# DSP.net
KiCad netlist of a schematic drawn in Altium Designer
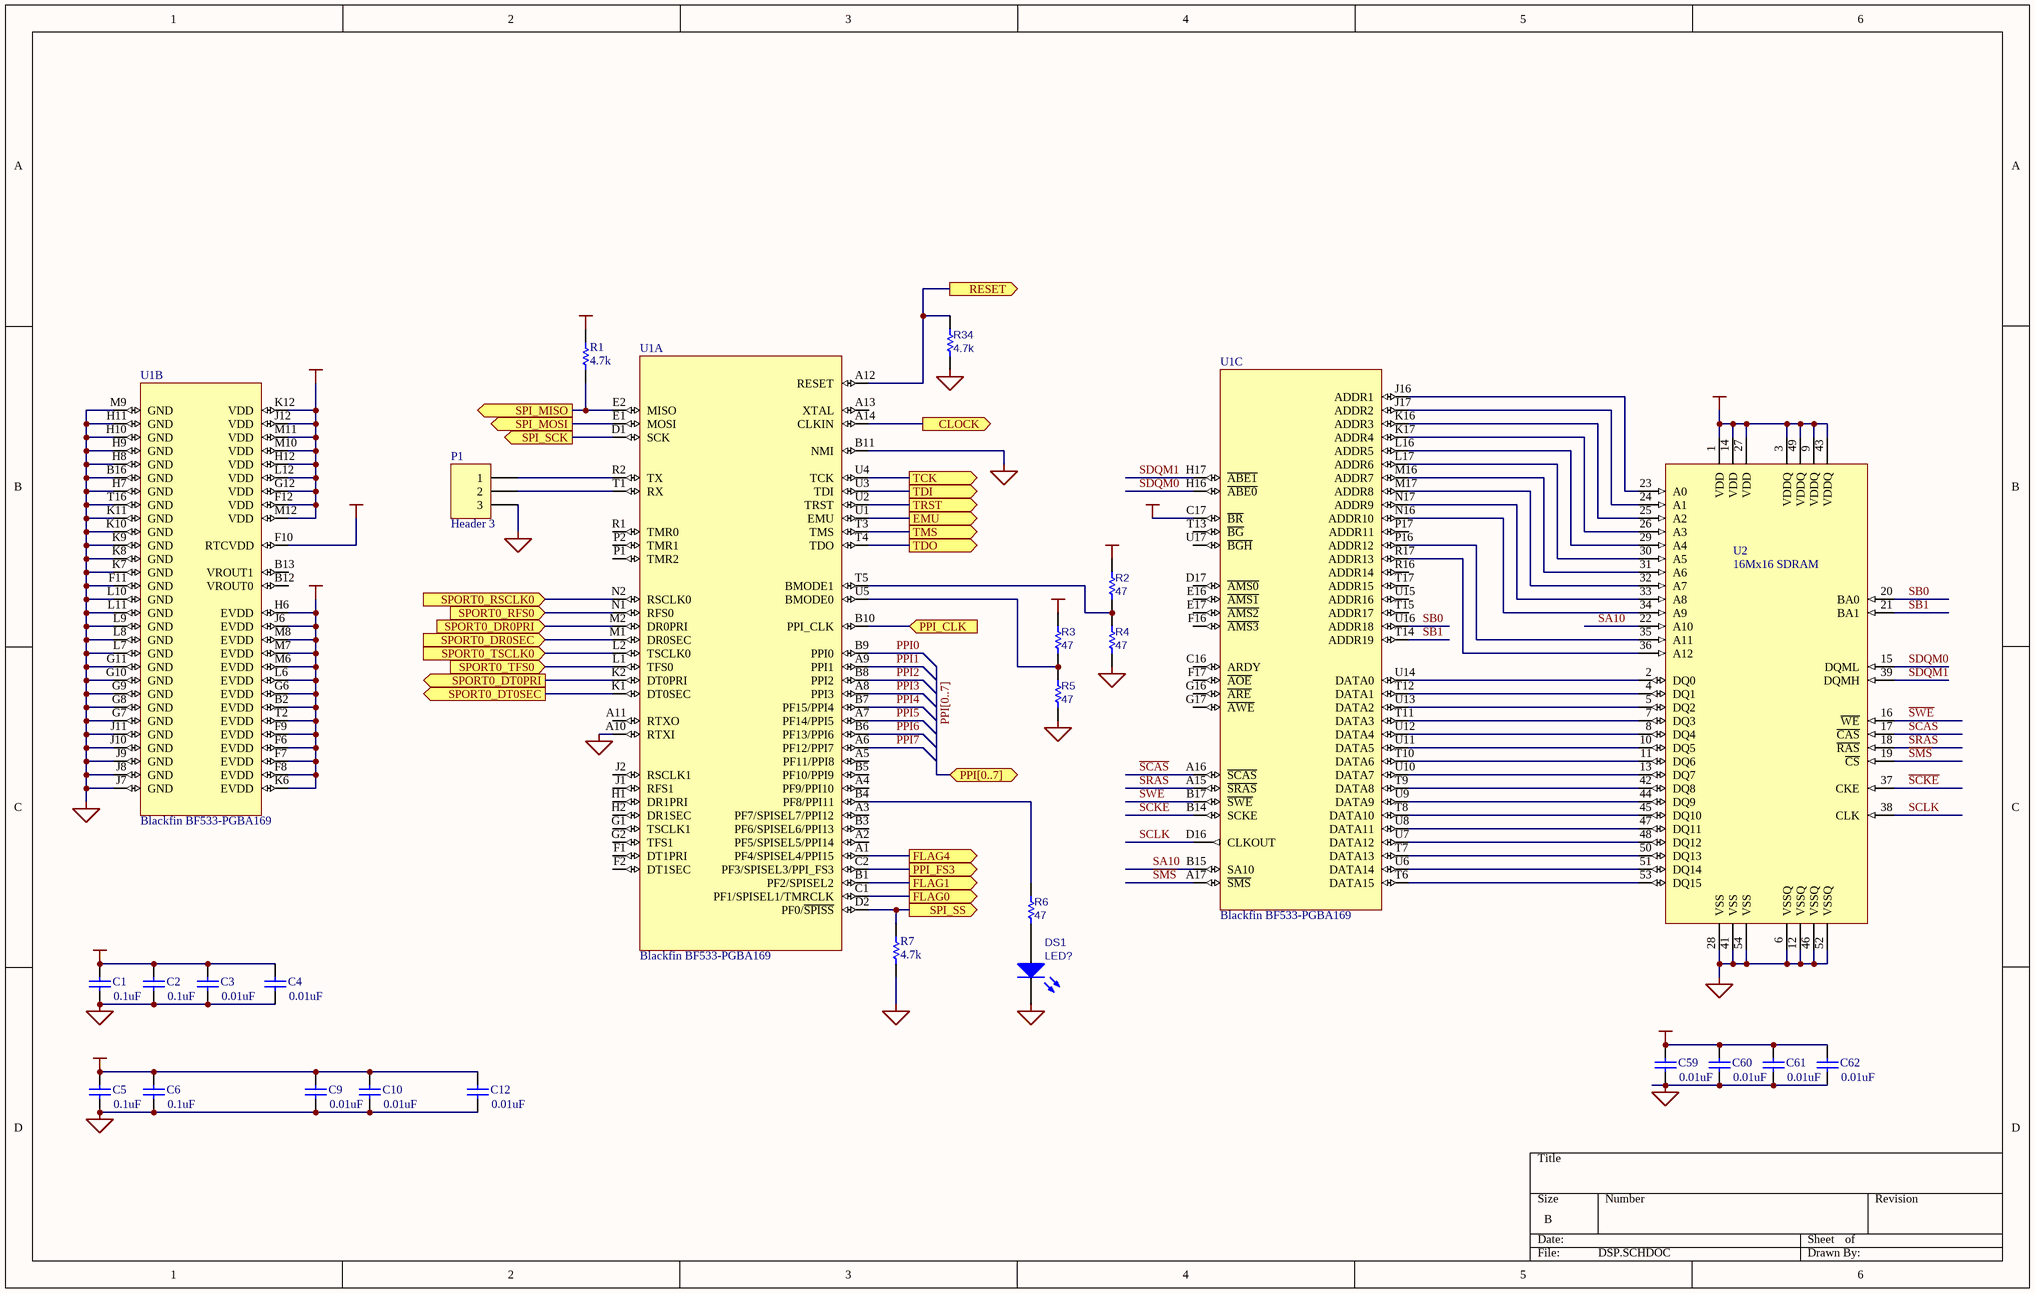
[diagram p0: DSP.SCHDOC]

(export (version "E")
  (design (tool "Eeschema 10.0.6"))
  (components
    (comp (ref "C1")
      (value "0.1uF")
      (footprint "CC1608-0603")
      (description "Capacitor")
      (fields (field (name "Comment") "Cap") (field (name "PUBLISHER") "Altium Limited"))
      (libsource (lib "Miscellaneous Devices") (part "Cap"))
    )
    (comp (ref "C2")
      (value "0.1uF")
      (footprint "CC1608-0603")
      (description "Capacitor")
      (fields (field (name "Comment") "Cap") (field (name "PUBLISHER") "Altium Limited"))
      (libsource (lib "Miscellaneous Devices") (part "Cap"))
    )
    (comp (ref "C3")
      (value "0.01uF")
      (footprint "CC1005-0402")
      (description "Capacitor")
      (fields (field (name "Comment") "Cap") (field (name "PUBLISHER") "Altium Limited"))
      (libsource (lib "Miscellaneous Devices") (part "Cap"))
    )
    (comp (ref "C4")
      (value "0.01uF")
      (footprint "CC1005-0402")
      (description "Capacitor")
      (fields (field (name "Comment") "Cap") (field (name "PUBLISHER") "Altium Limited"))
      (libsource (lib "Miscellaneous Devices") (part "Cap"))
    )
    (comp (ref "C5")
      (value "0.1uF")
      (footprint "CC1608-0603")
      (description "Capacitor")
      (fields (field (name "Comment") "Cap") (field (name "PUBLISHER") "Altium Limited"))
      (libsource (lib "Miscellaneous Devices") (part "Cap"))
    )
    (comp (ref "C6")
      (value "0.1uF")
      (footprint "CC1608-0603")
      (description "Capacitor")
      (fields (field (name "Comment") "Cap") (field (name "PUBLISHER") "Altium Limited"))
      (libsource (lib "Miscellaneous Devices") (part "Cap"))
    )
    (comp (ref "C9")
      (value "0.01uF")
      (footprint "CC1005-0402")
      (description "Capacitor")
      (fields (field (name "Comment") "Cap") (field (name "PUBLISHER") "Altium Limited"))
      (libsource (lib "Miscellaneous Devices") (part "Cap"))
    )
    (comp (ref "C10")
      (value "0.01uF")
      (footprint "CC1005-0402")
      (description "Capacitor")
      (fields (field (name "Comment") "Cap") (field (name "PUBLISHER") "Altium Limited"))
      (libsource (lib "Miscellaneous Devices") (part "Cap"))
    )
    (comp (ref "C12")
      (value "0.01uF")
      (footprint "CC1005-0402")
      (description "Capacitor")
      (fields (field (name "Comment") "Cap") (field (name "PUBLISHER") "Altium Limited"))
      (libsource (lib "Miscellaneous Devices") (part "Cap"))
    )
    (comp (ref "C59")
      (value "0.01uF")
      (footprint "CC1005-0402")
      (description "Capacitor")
      (fields (field (name "Comment") "Cap") (field (name "PUBLISHER") "Altium Limited"))
      (libsource (lib "Miscellaneous Devices") (part "Cap"))
    )
    (comp (ref "C60")
      (value "0.01uF")
      (footprint "CC1005-0402")
      (description "Capacitor")
      (fields (field (name "Comment") "Cap") (field (name "PUBLISHER") "Altium Limited"))
      (libsource (lib "Miscellaneous Devices") (part "Cap"))
    )
    (comp (ref "C61")
      (value "0.01uF")
      (footprint "CC1005-0402")
      (description "Capacitor")
      (fields (field (name "Comment") "Cap") (field (name "PUBLISHER") "Altium Limited"))
      (libsource (lib "Miscellaneous Devices") (part "Cap"))
    )
    (comp (ref "C62")
      (value "0.01uF")
      (footprint "CC1005-0402")
      (description "Capacitor")
      (fields (field (name "Comment") "Cap") (field (name "PUBLISHER") "Altium Limited"))
      (libsource (lib "Miscellaneous Devices") (part "Cap"))
    )
    (comp (ref "DS1")
      (value "LED?")
      (footprint "SMD _LED")
      (description "Typical BLUE SiC LED")
      (fields (field (name "PUBLISHER") "Altium Limited"))
      (libsource (lib "Miscellaneous Devices") (part "LED3"))
    )
    (comp (ref "P1")
      (value "Header 3")
      (footprint "HDR1X3")
      (description "Header, 3-Pin")
      (fields (field (name "PUBLISHER") "Altium Limited"))
      (libsource (lib "Miscellaneous Connectors") (part "Header 3"))
    )
    (comp (ref "R1")
      (value "4.7k")
      (footprint "CR1608-0603")
      (description "Resistor")
      (fields (field (name "PUBLISHER") "Altium Limited"))
      (libsource (lib "Miscellaneous Devices") (part "Res1"))
    )
    (comp (ref "R2")
      (value "47")
      (footprint "CR1608-0603")
      (description "Resistor")
      (fields
        (field (name "MANUFACTURER") "Generic Components")
        (field (name "Comment") "Res1")
        (field (name "PUBLISHER") "Altium Limited")
      )
      (libsource (lib "Miscellaneous Devices") (part "Res1"))
    )
    (comp (ref "R3")
      (value "47")
      (footprint "CR1608-0603")
      (description "Resistor")
      (fields
        (field (name "MANUFACTURER") "Generic Components")
        (field (name "Comment") "Res1")
        (field (name "PUBLISHER") "Altium Limited")
      )
      (libsource (lib "Miscellaneous Devices") (part "Res1"))
    )
    (comp (ref "R4")
      (value "47")
      (footprint "CR1608-0603")
      (description "Resistor")
      (fields
        (field (name "MANUFACTURER") "Generic Components")
        (field (name "Comment") "Res1")
        (field (name "PUBLISHER") "Altium Limited")
      )
      (libsource (lib "Miscellaneous Devices") (part "Res1"))
    )
    (comp (ref "R5")
      (value "47")
      (footprint "CR1608-0603")
      (description "Resistor")
      (fields
        (field (name "MANUFACTURER") "Generic Components")
        (field (name "Comment") "Res1")
        (field (name "PUBLISHER") "Altium Limited")
      )
      (libsource (lib "Miscellaneous Devices") (part "Res1"))
    )
    (comp (ref "R6")
      (value "47")
      (footprint "CR1608-0603")
      (description "Resistor")
      (fields
        (field (name "MANUFACTURER") "Generic Components")
        (field (name "Comment") "Res1")
        (field (name "PUBLISHER") "Altium Limited")
      )
      (libsource (lib "Miscellaneous Devices") (part "Res1"))
    )
    (comp (ref "R7")
      (value "4.7k")
      (footprint "CR1608-0603")
      (description "Resistor")
      (fields (field (name "PUBLISHER") "Altium Limited"))
      (libsource (lib "Miscellaneous Devices") (part "Res1"))
    )
    (comp (ref "R34")
      (value "4.7k")
      (footprint "CR1608-0603")
      (description "Resistor")
      (fields
        (field (name "MANUFACTURER") "Generic Components")
        (field (name "Comment") "Res1")
        (field (name "PUBLISHER") "Altium Limited")
      )
      (libsource (lib "Miscellaneous Devices") (part "Res1"))
    )
    (comp (ref "U1")
      (value "Blackfin BF533-PGBA169")
      (footprint "AD PBGA-169")
      (description "Analog Devices Blackfin")
      (libsource (lib "parts") (part "ADSP-BF53x-PBGA169"))
    )
    (comp (ref "U2")
      (value "16Mx16 SDRAM")
      (footprint "SO-G54/X.5")
      (description "Micron 16Mbitx16 SDRAM")
      (libsource (lib "parts") (part "MT48LC16M16A2TG"))
    )
  )
  (nets
    (net (code "1") (name "+1.2VCC") (class "Default")
      (node (ref "C1") (pin "2") (pinfunction "2_2") (pintype "passive"))
      (node (ref "C2") (pin "2") (pinfunction "2_2") (pintype "passive"))
      (node (ref "C3") (pin "2") (pinfunction "2_2") (pintype "passive"))
      (node (ref "C4") (pin "2") (pinfunction "2_2") (pintype "passive"))
      (node (ref "U1") (pin "F12") (pinfunction "VDD_F12") (pintype "bidirectional"))
      (node (ref "U1") (pin "G12") (pinfunction "VDD_G12") (pintype "bidirectional"))
      (node (ref "U1") (pin "H12") (pinfunction "VDD_H12") (pintype "bidirectional"))
      (node (ref "U1") (pin "J12") (pinfunction "VDD_J12") (pintype "bidirectional"))
      (node (ref "U1") (pin "K12") (pinfunction "VDD_K12") (pintype "bidirectional"))
      (node (ref "U1") (pin "L12") (pinfunction "VDD_L12") (pintype "bidirectional"))
      (node (ref "U1") (pin "M10") (pinfunction "VDD_M10") (pintype "bidirectional"))
      (node (ref "U1") (pin "M11") (pinfunction "VDD_M11") (pintype "bidirectional"))
      (node (ref "U1") (pin "M12") (pinfunction "VDD_M12") (pintype "bidirectional"))
    )
    (net (code "2") (name "/CLOCK") (class "Default")
      (node (ref "U1") (pin "A14") (pinfunction "CLKIN_A14") (pintype "bidirectional"))
    )
    (net (code "3") (name "/EMU") (class "Default")
      (node (ref "U1") (pin "U1") (pinfunction "EMU_U1") (pintype "bidirectional"))
    )
    (net (code "4") (name "/FLAG0") (class "Default")
      (node (ref "U1") (pin "C1") (pinfunction "PF1/SPISEL1/TMRCLK_C1") (pintype "bidirectional"))
    )
    (net (code "5") (name "/FLAG1") (class "Default")
      (node (ref "U1") (pin "B1") (pinfunction "PF2/SPISEL2_B1") (pintype "bidirectional"))
    )
    (net (code "6") (name "/FLAG4") (class "Default")
      (node (ref "U1") (pin "A1") (pinfunction "PF4/SPISEL4/PPI15_A1") (pintype "bidirectional"))
    )
    (net (code "7") (name "/PPI0") (class "Default")
      (node (ref "U1") (pin "B9") (pinfunction "PPI0_B9") (pintype "bidirectional"))
    )
    (net (code "8") (name "/PPI1") (class "Default")
      (node (ref "U1") (pin "A9") (pinfunction "PPI1_A9") (pintype "bidirectional"))
    )
    (net (code "9") (name "/PPI2") (class "Default")
      (node (ref "U1") (pin "B8") (pinfunction "PPI2_B8") (pintype "bidirectional"))
    )
    (net (code "10") (name "/PPI3") (class "Default")
      (node (ref "U1") (pin "A8") (pinfunction "PPI3_A8") (pintype "bidirectional"))
    )
    (net (code "11") (name "/PPI4") (class "Default")
      (node (ref "U1") (pin "B7") (pinfunction "PF15/PPI4_B7") (pintype "bidirectional"))
    )
    (net (code "12") (name "/PPI5") (class "Default")
      (node (ref "U1") (pin "A7") (pinfunction "PF14/PPI5_A7") (pintype "bidirectional"))
    )
    (net (code "13") (name "/PPI6") (class "Default")
      (node (ref "U1") (pin "B6") (pinfunction "PF13/PPI6_B6") (pintype "bidirectional"))
    )
    (net (code "14") (name "/PPI7") (class "Default")
      (node (ref "U1") (pin "A6") (pinfunction "PF12/PPI7_A6") (pintype "bidirectional"))
    )
    (net (code "16") (name "/PPI_CLK") (class "Default")
      (node (ref "U1") (pin "B10") (pinfunction "PPI_CLK_B10") (pintype "bidirectional"))
    )
    (net (code "17") (name "/PPI_FS3") (class "Default")
      (node (ref "U1") (pin "C2") (pinfunction "PF3/SPISEL3/PPI_FS3_C2") (pintype "bidirectional"))
    )
    (net (code "18") (name "/RESET") (class "Default")
      (node (ref "R34") (pin "1") (pinfunction "1_1") (pintype "passive"))
      (node (ref "U1") (pin "A12") (pinfunction "RESET_A12") (pintype "bidirectional"))
    )
    (net (code "19") (name "/SA10") (class "Default")
      (node (ref "U1") (pin "B15") (pinfunction "SA10_B15") (pintype "bidirectional"))
      (node (ref "U2") (pin "22") (pinfunction "A10_22") (pintype "input"))
    )
    (net (code "20") (name "/SB0") (class "Default")
      (node (ref "U1") (pin "U16") (pinfunction "ADDR18_U16") (pintype "bidirectional"))
      (node (ref "U2") (pin "20") (pinfunction "BA0_20") (pintype "input"))
    )
    (net (code "21") (name "/SB1") (class "Default")
      (node (ref "U1") (pin "T14") (pinfunction "ADDR19_T14") (pintype "bidirectional"))
      (node (ref "U2") (pin "21") (pinfunction "BA1_21") (pintype "input"))
    )
    (net (code "22") (name "/SCLK") (class "Default")
      (node (ref "U1") (pin "D16") (pinfunction "CLKOUT_D16") (pintype "output"))
      (node (ref "U2") (pin "38") (pinfunction "CLK_38") (pintype "input"))
    )
    (net (code "23") (name "/SDQM0") (class "Default")
      (node (ref "U1") (pin "H16") (pinfunction "~{ABE0}_H16") (pintype "bidirectional"))
      (node (ref "U2") (pin "15") (pinfunction "DQML_15") (pintype "input"))
    )
    (net (code "24") (name "/SDQM1") (class "Default")
      (node (ref "U1") (pin "H17") (pinfunction "~{ABE1}_H17") (pintype "bidirectional"))
      (node (ref "U2") (pin "39") (pinfunction "DQMH_39") (pintype "input"))
    )
    (net (code "25") (name "/SPI_MISO") (class "Default")
      (node (ref "R1") (pin "1") (pinfunction "1_1") (pintype "passive"))
      (node (ref "U1") (pin "E2") (pinfunction "MISO_E2") (pintype "bidirectional"))
    )
    (net (code "26") (name "/SPI_MOSI") (class "Default")
      (node (ref "U1") (pin "E1") (pinfunction "MOSI_E1") (pintype "bidirectional"))
    )
    (net (code "27") (name "/SPI_SCK") (class "Default")
      (node (ref "U1") (pin "D1") (pinfunction "SCK_D1") (pintype "bidirectional"))
    )
    (net (code "28") (name "/SPI_SS") (class "Default")
      (node (ref "R7") (pin "2") (pinfunction "2_2") (pintype "passive"))
      (node (ref "U1") (pin "D2") (pinfunction "PF0/~{SPISS}_D2") (pintype "bidirectional"))
    )
    (net (code "29") (name "/SPORT0_DR0PRI") (class "Default")
      (node (ref "U1") (pin "M2") (pinfunction "DR0PRI_M2") (pintype "bidirectional"))
    )
    (net (code "30") (name "/SPORT0_DR0SEC") (class "Default")
      (node (ref "U1") (pin "M1") (pinfunction "DR0SEC_M1") (pintype "bidirectional"))
    )
    (net (code "31") (name "/SPORT0_DT0PRI") (class "Default")
      (node (ref "U1") (pin "K2") (pinfunction "DT0PRI_K2") (pintype "bidirectional"))
    )
    (net (code "32") (name "/SPORT0_DT0SEC") (class "Default")
      (node (ref "U1") (pin "K1") (pinfunction "DT0SEC_K1") (pintype "bidirectional"))
    )
    (net (code "33") (name "/SPORT0_RFS0") (class "Default")
      (node (ref "U1") (pin "N1") (pinfunction "RFS0_N1") (pintype "bidirectional"))
    )
    (net (code "34") (name "/SPORT0_RSCLK0") (class "Default")
      (node (ref "U1") (pin "N2") (pinfunction "RSCLK0_N2") (pintype "bidirectional"))
    )
    (net (code "35") (name "/SPORT0_TFS0") (class "Default")
      (node (ref "U1") (pin "L1") (pinfunction "TFS0_L1") (pintype "bidirectional"))
    )
    (net (code "36") (name "/SPORT0_TSCLK0") (class "Default")
      (node (ref "U1") (pin "L2") (pinfunction "TSCLK0_L2") (pintype "bidirectional"))
    )
    (net (code "37") (name "/TCK") (class "Default")
      (node (ref "U1") (pin "U4") (pinfunction "TCK_U4") (pintype "bidirectional"))
    )
    (net (code "38") (name "/TDI") (class "Default")
      (node (ref "U1") (pin "U3") (pinfunction "TDI_U3") (pintype "bidirectional"))
    )
    (net (code "39") (name "/TDO") (class "Default")
      (node (ref "U1") (pin "T4") (pinfunction "TDO_T4") (pintype "bidirectional"))
    )
    (net (code "40") (name "/TMS") (class "Default")
      (node (ref "U1") (pin "T3") (pinfunction "TMS_T3") (pintype "bidirectional"))
    )
    (net (code "41") (name "/TRST") (class "Default")
      (node (ref "U1") (pin "U2") (pinfunction "TRST_U2") (pintype "bidirectional"))
    )
    (net (code "42") (name "/~{SCAS}") (class "Default")
      (node (ref "U1") (pin "A16") (pinfunction "~{SCAS}_A16") (pintype "bidirectional"))
      (node (ref "U2") (pin "17") (pinfunction "~{CAS}_17") (pintype "input"))
    )
    (net (code "43") (name "/~{SCKE}") (class "Default")
      (node (ref "U1") (pin "B14") (pinfunction "SCKE_B14") (pintype "bidirectional"))
      (node (ref "U2") (pin "37") (pinfunction "CKE_37") (pintype "input"))
    )
    (net (code "44") (name "/~{SMS}") (class "Default")
      (node (ref "U1") (pin "A17") (pinfunction "~{SMS}_A17") (pintype "bidirectional"))
      (node (ref "U2") (pin "19") (pinfunction "~{CS}_19") (pintype "input"))
    )
    (net (code "45") (name "/~{SRAS}") (class "Default")
      (node (ref "U1") (pin "A15") (pinfunction "~{SRAS}_A15") (pintype "bidirectional"))
      (node (ref "U2") (pin "18") (pinfunction "~{RAS}_18") (pintype "input"))
    )
    (net (code "46") (name "/~{SWE}") (class "Default")
      (node (ref "U1") (pin "B17") (pinfunction "~{SWE}_B17") (pintype "bidirectional"))
      (node (ref "U2") (pin "16") (pinfunction "~{WE}_16") (pintype "input"))
    )
    (net (code "47") (name "GND") (class "Default")
      (node (ref "C1") (pin "1") (pinfunction "1_1") (pintype "passive"))
      (node (ref "C10") (pin "1") (pinfunction "1_1") (pintype "passive"))
      (node (ref "C12") (pin "1") (pinfunction "1_1") (pintype "passive"))
      (node (ref "C2") (pin "1") (pinfunction "1_1") (pintype "passive"))
      (node (ref "C3") (pin "1") (pinfunction "1_1") (pintype "passive"))
      (node (ref "C4") (pin "1") (pinfunction "1_1") (pintype "passive"))
      (node (ref "C5") (pin "1") (pinfunction "1_1") (pintype "passive"))
      (node (ref "C59") (pin "1") (pinfunction "1_1") (pintype "passive"))
      (node (ref "C6") (pin "1") (pinfunction "1_1") (pintype "passive"))
      (node (ref "C60") (pin "1") (pinfunction "1_1") (pintype "passive"))
      (node (ref "C61") (pin "1") (pinfunction "1_1") (pintype "passive"))
      (node (ref "C62") (pin "1") (pinfunction "1_1") (pintype "passive"))
      (node (ref "C9") (pin "1") (pinfunction "1_1") (pintype "passive"))
      (node (ref "DS1") (pin "2") (pinfunction "K_2") (pintype "passive"))
      (node (ref "P1") (pin "3") (pinfunction "3_3") (pintype "passive"))
      (node (ref "R34") (pin "2") (pinfunction "2_2") (pintype "passive"))
      (node (ref "R4") (pin "2") (pinfunction "2_2") (pintype "passive"))
      (node (ref "R5") (pin "2") (pinfunction "2_2") (pintype "passive"))
      (node (ref "R7") (pin "1") (pinfunction "1_1") (pintype "passive"))
      (node (ref "U1") (pin "A10") (pinfunction "RTXI_A10") (pintype "bidirectional"))
      (node (ref "U1") (pin "B11") (pinfunction "NMI_B11") (pintype "bidirectional"))
      (node (ref "U1") (pin "B16") (pinfunction "GND_B16") (pintype "bidirectional"))
      (node (ref "U1") (pin "F11") (pinfunction "GND_F11") (pintype "bidirectional"))
      (node (ref "U1") (pin "G10") (pinfunction "GND_G10") (pintype "bidirectional"))
      (node (ref "U1") (pin "G11") (pinfunction "GND_G11") (pintype "bidirectional"))
      (node (ref "U1") (pin "G7") (pinfunction "GND_G7") (pintype "bidirectional"))
      (node (ref "U1") (pin "G8") (pinfunction "GND_G8") (pintype "bidirectional"))
      (node (ref "U1") (pin "G9") (pinfunction "GND_G9") (pintype "bidirectional"))
      (node (ref "U1") (pin "H10") (pinfunction "GND_H10") (pintype "bidirectional"))
      (node (ref "U1") (pin "H11") (pinfunction "GND_H11") (pintype "bidirectional"))
      (node (ref "U1") (pin "H7") (pinfunction "GND_H7") (pintype "bidirectional"))
      (node (ref "U1") (pin "H8") (pinfunction "GND_H8") (pintype "bidirectional"))
      (node (ref "U1") (pin "H9") (pinfunction "GND_H9") (pintype "bidirectional"))
      (node (ref "U1") (pin "J10") (pinfunction "GND_J10") (pintype "bidirectional"))
      (node (ref "U1") (pin "J11") (pinfunction "GND_J11") (pintype "bidirectional"))
      (node (ref "U1") (pin "J7") (pinfunction "GND_J7") (pintype "bidirectional"))
      (node (ref "U1") (pin "J8") (pinfunction "GND_J8") (pintype "bidirectional"))
      (node (ref "U1") (pin "J9") (pinfunction "GND_J9") (pintype "bidirectional"))
      (node (ref "U1") (pin "K10") (pinfunction "GND_K10") (pintype "bidirectional"))
      (node (ref "U1") (pin "K11") (pinfunction "GND_K11") (pintype "bidirectional"))
      (node (ref "U1") (pin "K7") (pinfunction "GND_K7") (pintype "bidirectional"))
      (node (ref "U1") (pin "K8") (pinfunction "GND_K8") (pintype "bidirectional"))
      (node (ref "U1") (pin "K9") (pinfunction "GND_K9") (pintype "bidirectional"))
      (node (ref "U1") (pin "L10") (pinfunction "GND_L10") (pintype "bidirectional"))
      (node (ref "U1") (pin "L11") (pinfunction "GND_L11") (pintype "bidirectional"))
      (node (ref "U1") (pin "L7") (pinfunction "GND_L7") (pintype "bidirectional"))
      (node (ref "U1") (pin "L8") (pinfunction "GND_L8") (pintype "bidirectional"))
      (node (ref "U1") (pin "L9") (pinfunction "GND_L9") (pintype "bidirectional"))
      (node (ref "U1") (pin "M9") (pinfunction "GND_M9") (pintype "bidirectional"))
      (node (ref "U1") (pin "T16") (pinfunction "GND_T16") (pintype "bidirectional"))
      (node (ref "U2") (pin "12") (pinfunction "VSSQ_12") (pintype "power_in"))
      (node (ref "U2") (pin "28") (pinfunction "VSS_28") (pintype "power_in"))
      (node (ref "U2") (pin "41") (pinfunction "VSS_41") (pintype "power_in"))
      (node (ref "U2") (pin "46") (pinfunction "VSSQ_46") (pintype "power_in"))
      (node (ref "U2") (pin "52") (pinfunction "VSSQ_52") (pintype "power_in"))
      (node (ref "U2") (pin "54") (pinfunction "VSS_54") (pintype "power_in"))
      (node (ref "U2") (pin "6") (pinfunction "VSSQ_6") (pintype "power_in"))
    )
    (net (code "48") (name "Net-(DS1-A)") (class "Default")
      (node (ref "DS1") (pin "1") (pinfunction "A_1") (pintype "passive"))
      (node (ref "R6") (pin "2") (pinfunction "2_2") (pintype "passive"))
    )
    (net (code "49") (name "Net-(U1A-BMODE0)") (class "Default")
      (node (ref "R3") (pin "2") (pinfunction "2_2") (pintype "passive"))
      (node (ref "R5") (pin "1") (pinfunction "1_1") (pintype "passive"))
      (node (ref "U1") (pin "U5") (pinfunction "BMODE0_U5") (pintype "bidirectional"))
    )
    (net (code "50") (name "Net-(U1A-BMODE1)") (class "Default")
      (node (ref "R2") (pin "2") (pinfunction "2_2") (pintype "passive"))
      (node (ref "R4") (pin "1") (pinfunction "1_1") (pintype "passive"))
      (node (ref "U1") (pin "T5") (pinfunction "BMODE1_T5") (pintype "bidirectional"))
    )
    (net (code "51") (name "Net-(U1A-PF8{slash}PPI11)") (class "Default")
      (node (ref "R6") (pin "1") (pinfunction "1_1") (pintype "passive"))
      (node (ref "U1") (pin "B4") (pinfunction "PF8/PPI11_B4") (pintype "bidirectional"))
    )
    (net (code "52") (name "Net-(U1A-RX)") (class "Default")
      (node (ref "P1") (pin "2") (pinfunction "2_2") (pintype "passive"))
      (node (ref "U1") (pin "T1") (pinfunction "RX_T1") (pintype "bidirectional"))
    )
    (net (code "53") (name "Net-(U1A-TX)") (class "Default")
      (node (ref "P1") (pin "1") (pinfunction "1_1") (pintype "passive"))
      (node (ref "U1") (pin "R2") (pinfunction "TX_R2") (pintype "bidirectional"))
    )
    (net (code "54") (name "Net-(U1C-ADDR1)") (class "Default")
      (node (ref "U1") (pin "J16") (pinfunction "ADDR1_J16") (pintype "bidirectional"))
      (node (ref "U2") (pin "23") (pinfunction "A0_23") (pintype "input"))
    )
    (net (code "55") (name "Net-(U1C-ADDR2)") (class "Default")
      (node (ref "U1") (pin "J17") (pinfunction "ADDR2_J17") (pintype "bidirectional"))
      (node (ref "U2") (pin "24") (pinfunction "A1_24") (pintype "input"))
    )
    (net (code "56") (name "Net-(U1C-ADDR3)") (class "Default")
      (node (ref "U1") (pin "K16") (pinfunction "ADDR3_K16") (pintype "bidirectional"))
      (node (ref "U2") (pin "25") (pinfunction "A2_25") (pintype "input"))
    )
    (net (code "57") (name "Net-(U1C-ADDR4)") (class "Default")
      (node (ref "U1") (pin "K17") (pinfunction "ADDR4_K17") (pintype "bidirectional"))
      (node (ref "U2") (pin "26") (pinfunction "A3_26") (pintype "input"))
    )
    (net (code "58") (name "Net-(U1C-ADDR5)") (class "Default")
      (node (ref "U1") (pin "L16") (pinfunction "ADDR5_L16") (pintype "bidirectional"))
      (node (ref "U2") (pin "29") (pinfunction "A4_29") (pintype "input"))
    )
    (net (code "59") (name "Net-(U1C-ADDR6)") (class "Default")
      (node (ref "U1") (pin "L17") (pinfunction "ADDR6_L17") (pintype "bidirectional"))
      (node (ref "U2") (pin "30") (pinfunction "A5_30") (pintype "input"))
    )
    (net (code "60") (name "Net-(U1C-ADDR7)") (class "Default")
      (node (ref "U1") (pin "M16") (pinfunction "ADDR7_M16") (pintype "bidirectional"))
      (node (ref "U2") (pin "31") (pinfunction "A6_31") (pintype "input"))
    )
    (net (code "61") (name "Net-(U1C-ADDR8)") (class "Default")
      (node (ref "U1") (pin "M17") (pinfunction "ADDR8_M17") (pintype "bidirectional"))
      (node (ref "U2") (pin "32") (pinfunction "A7_32") (pintype "input"))
    )
    (net (code "62") (name "Net-(U1C-ADDR9)") (class "Default")
      (node (ref "U1") (pin "N17") (pinfunction "ADDR9_N17") (pintype "bidirectional"))
      (node (ref "U2") (pin "33") (pinfunction "A8_33") (pintype "input"))
    )
    (net (code "63") (name "Net-(U1C-ADDR10)") (class "Default")
      (node (ref "U1") (pin "N16") (pinfunction "ADDR10_N16") (pintype "bidirectional"))
      (node (ref "U2") (pin "34") (pinfunction "A9_34") (pintype "input"))
    )
    (net (code "64") (name "Net-(U1C-ADDR12)") (class "Default")
      (node (ref "U1") (pin "P16") (pinfunction "ADDR12_P16") (pintype "bidirectional"))
      (node (ref "U2") (pin "35") (pinfunction "A11_35") (pintype "input"))
    )
    (net (code "65") (name "Net-(U1C-ADDR13)") (class "Default")
      (node (ref "U1") (pin "R17") (pinfunction "ADDR13_R17") (pintype "bidirectional"))
      (node (ref "U2") (pin "36") (pinfunction "A12_36") (pintype "input"))
    )
    (net (code "66") (name "Net-(U1C-DATA0)") (class "Default")
      (node (ref "U1") (pin "U14") (pinfunction "DATA0_U14") (pintype "bidirectional"))
      (node (ref "U2") (pin "2") (pinfunction "DQ0_2") (pintype "bidirectional"))
    )
    (net (code "67") (name "Net-(U1C-DATA1)") (class "Default")
      (node (ref "U1") (pin "T12") (pinfunction "DATA1_T12") (pintype "bidirectional"))
      (node (ref "U2") (pin "4") (pinfunction "DQ1_4") (pintype "bidirectional"))
    )
    (net (code "68") (name "Net-(U1C-DATA2)") (class "Default")
      (node (ref "U1") (pin "U13") (pinfunction "DATA2_U13") (pintype "bidirectional"))
      (node (ref "U2") (pin "5") (pinfunction "DQ2_5") (pintype "bidirectional"))
    )
    (net (code "69") (name "Net-(U1C-DATA3)") (class "Default")
      (node (ref "U1") (pin "T11") (pinfunction "DATA3_T11") (pintype "bidirectional"))
      (node (ref "U2") (pin "7") (pinfunction "DQ3_7") (pintype "bidirectional"))
    )
    (net (code "70") (name "Net-(U1C-DATA4)") (class "Default")
      (node (ref "U1") (pin "U12") (pinfunction "DATA4_U12") (pintype "bidirectional"))
      (node (ref "U2") (pin "8") (pinfunction "DQ4_8") (pintype "bidirectional"))
    )
    (net (code "71") (name "Net-(U1C-DATA5)") (class "Default")
      (node (ref "U1") (pin "U11") (pinfunction "DATA5_U11") (pintype "bidirectional"))
      (node (ref "U2") (pin "10") (pinfunction "DQ5_10") (pintype "bidirectional"))
    )
    (net (code "72") (name "Net-(U1C-DATA6)") (class "Default")
      (node (ref "U1") (pin "T10") (pinfunction "DATA6_T10") (pintype "bidirectional"))
      (node (ref "U2") (pin "11") (pinfunction "DQ6_11") (pintype "bidirectional"))
    )
    (net (code "73") (name "Net-(U1C-DATA7)") (class "Default")
      (node (ref "U1") (pin "U10") (pinfunction "DATA7_U10") (pintype "bidirectional"))
      (node (ref "U2") (pin "13") (pinfunction "DQ7_13") (pintype "bidirectional"))
    )
    (net (code "74") (name "Net-(U1C-DATA8)") (class "Default")
      (node (ref "U1") (pin "T9") (pinfunction "DATA8_T9") (pintype "bidirectional"))
      (node (ref "U2") (pin "42") (pinfunction "DQ8_42") (pintype "bidirectional"))
    )
    (net (code "75") (name "Net-(U1C-DATA9)") (class "Default")
      (node (ref "U1") (pin "U9") (pinfunction "DATA9_U9") (pintype "bidirectional"))
      (node (ref "U2") (pin "44") (pinfunction "DQ9_44") (pintype "bidirectional"))
    )
    (net (code "76") (name "Net-(U1C-DATA10)") (class "Default")
      (node (ref "U1") (pin "T8") (pinfunction "DATA10_T8") (pintype "bidirectional"))
      (node (ref "U2") (pin "45") (pinfunction "DQ10_45") (pintype "bidirectional"))
    )
    (net (code "77") (name "Net-(U1C-DATA11)") (class "Default")
      (node (ref "U1") (pin "U8") (pinfunction "DATA11_U8") (pintype "bidirectional"))
      (node (ref "U2") (pin "47") (pinfunction "DQ11_47") (pintype "bidirectional"))
    )
    (net (code "78") (name "Net-(U1C-DATA12)") (class "Default")
      (node (ref "U1") (pin "U7") (pinfunction "DATA12_U7") (pintype "bidirectional"))
      (node (ref "U2") (pin "48") (pinfunction "DQ12_48") (pintype "bidirectional"))
    )
    (net (code "79") (name "Net-(U1C-DATA13)") (class "Default")
      (node (ref "U1") (pin "T7") (pinfunction "DATA13_T7") (pintype "bidirectional"))
      (node (ref "U2") (pin "50") (pinfunction "DQ13_50") (pintype "bidirectional"))
    )
    (net (code "80") (name "Net-(U1C-DATA14)") (class "Default")
      (node (ref "U1") (pin "U6") (pinfunction "DATA14_U6") (pintype "bidirectional"))
      (node (ref "U2") (pin "51") (pinfunction "DQ14_51") (pintype "bidirectional"))
    )
    (net (code "81") (name "Net-(U1C-DATA15)") (class "Default")
      (node (ref "U1") (pin "T6") (pinfunction "DATA15_T6") (pintype "bidirectional"))
      (node (ref "U2") (pin "53") (pinfunction "DQ15_53") (pintype "bidirectional"))
    )
    (net (code "82") (name "VCC") (class "Default")
      (node (ref "C10") (pin "2") (pinfunction "2_2") (pintype "passive"))
      (node (ref "C12") (pin "2") (pinfunction "2_2") (pintype "passive"))
      (node (ref "C5") (pin "2") (pinfunction "2_2") (pintype "passive"))
      (node (ref "C59") (pin "2") (pinfunction "2_2") (pintype "passive"))
      (node (ref "C6") (pin "2") (pinfunction "2_2") (pintype "passive"))
      (node (ref "C60") (pin "2") (pinfunction "2_2") (pintype "passive"))
      (node (ref "C61") (pin "2") (pinfunction "2_2") (pintype "passive"))
      (node (ref "C62") (pin "2") (pinfunction "2_2") (pintype "passive"))
      (node (ref "C9") (pin "2") (pinfunction "2_2") (pintype "passive"))
      (node (ref "R1") (pin "2") (pinfunction "2_2") (pintype "passive"))
      (node (ref "R2") (pin "1") (pinfunction "1_1") (pintype "passive"))
      (node (ref "R3") (pin "1") (pinfunction "1_1") (pintype "passive"))
      (node (ref "U1") (pin "B2") (pinfunction "EVDD_B2") (pintype "bidirectional"))
      (node (ref "U1") (pin "C17") (pinfunction "~{BR}_C17") (pintype "bidirectional"))
      (node (ref "U1") (pin "F10") (pinfunction "RTCVDD_F10") (pintype "bidirectional"))
      (node (ref "U1") (pin "F6") (pinfunction "EVDD_F6") (pintype "bidirectional"))
      (node (ref "U1") (pin "F7") (pinfunction "EVDD_F7") (pintype "bidirectional"))
      (node (ref "U1") (pin "F8") (pinfunction "EVDD_F8") (pintype "bidirectional"))
      (node (ref "U1") (pin "F9") (pinfunction "EVDD_F9") (pintype "bidirectional"))
      (node (ref "U1") (pin "G6") (pinfunction "EVDD_G6") (pintype "bidirectional"))
      (node (ref "U1") (pin "H6") (pinfunction "EVDD_H6") (pintype "bidirectional"))
      (node (ref "U1") (pin "J6") (pinfunction "EVDD_J6") (pintype "bidirectional"))
      (node (ref "U1") (pin "K6") (pinfunction "EVDD_K6") (pintype "bidirectional"))
      (node (ref "U1") (pin "L6") (pinfunction "EVDD_L6") (pintype "bidirectional"))
      (node (ref "U1") (pin "M6") (pinfunction "EVDD_M6") (pintype "bidirectional"))
      (node (ref "U1") (pin "M7") (pinfunction "EVDD_M7") (pintype "bidirectional"))
      (node (ref "U1") (pin "M8") (pinfunction "EVDD_M8") (pintype "bidirectional"))
      (node (ref "U1") (pin "T2") (pinfunction "EVDD_T2") (pintype "bidirectional"))
      (node (ref "U2") (pin "1") (pinfunction "VDD_1") (pintype "power_in"))
      (node (ref "U2") (pin "14") (pinfunction "VDD_14") (pintype "power_in"))
      (node (ref "U2") (pin "27") (pinfunction "VDD_27") (pintype "power_in"))
      (node (ref "U2") (pin "3") (pinfunction "VDDQ_3") (pintype "power_in"))
      (node (ref "U2") (pin "43") (pinfunction "VDDQ_43") (pintype "power_in"))
      (node (ref "U2") (pin "49") (pinfunction "VDDQ_49") (pintype "power_in"))
      (node (ref "U2") (pin "9") (pinfunction "VDDQ_9") (pintype "power_in"))
    )
    (net (code "83") (name "unconnected-(U1A-DR1PRI-PadH1)") (class "Default")
      (node (ref "U1") (pin "H1") (pinfunction "DR1PRI_H1") (pintype "bidirectional"))
    )
    (net (code "84") (name "unconnected-(U1A-DR1SEC-PadH2)") (class "Default")
      (node (ref "U1") (pin "H2") (pinfunction "DR1SEC_H2") (pintype "bidirectional"))
    )
    (net (code "85") (name "unconnected-(U1A-DT1PRI-PadF1)") (class "Default")
      (node (ref "U1") (pin "F1") (pinfunction "DT1PRI_F1") (pintype "bidirectional"))
    )
    (net (code "86") (name "unconnected-(U1A-DT1SEC-PadF2)") (class "Default")
      (node (ref "U1") (pin "F2") (pinfunction "DT1SEC_F2") (pintype "bidirectional"))
    )
    (net (code "87") (name "unconnected-(U1A-PF5{slash}SPISEL5{slash}PPI14-PadA2)") (class "Default")
      (node (ref "U1") (pin "A2") (pinfunction "PF5/SPISEL5/PPI14_A2") (pintype "bidirectional"))
    )
    (net (code "88") (name "unconnected-(U1A-PF6{slash}SPISEL6{slash}PPI13-PadB3)") (class "Default")
      (node (ref "U1") (pin "B3") (pinfunction "PF6/SPISEL6/PPI13_B3") (pintype "bidirectional"))
    )
    (net (code "89") (name "unconnected-(U1A-PF7{slash}SPISEL7{slash}PPI12-PadA3)") (class "Default")
      (node (ref "U1") (pin "A3") (pinfunction "PF7/SPISEL7/PPI12_A3") (pintype "bidirectional"))
    )
    (net (code "90") (name "unconnected-(U1A-PF9{slash}PPI10-PadA4)") (class "Default")
      (node (ref "U1") (pin "A4") (pinfunction "PF9/PPI10_A4") (pintype "bidirectional"))
    )
    (net (code "91") (name "unconnected-(U1A-PF10{slash}PPI9-PadB5)") (class "Default")
      (node (ref "U1") (pin "B5") (pinfunction "PF10/PPI9_B5") (pintype "bidirectional"))
    )
    (net (code "92") (name "unconnected-(U1A-PF11{slash}PPI8-PadA5)") (class "Default")
      (node (ref "U1") (pin "A5") (pinfunction "PF11/PPI8_A5") (pintype "bidirectional"))
    )
    (net (code "93") (name "unconnected-(U1A-RFS1-PadJ1)") (class "Default")
      (node (ref "U1") (pin "J1") (pinfunction "RFS1_J1") (pintype "bidirectional"))
    )
    (net (code "94") (name "unconnected-(U1A-RSCLK1-PadJ2)") (class "Default")
      (node (ref "U1") (pin "J2") (pinfunction "RSCLK1_J2") (pintype "bidirectional"))
    )
    (net (code "95") (name "unconnected-(U1A-RTXO-PadA11)") (class "Default")
      (node (ref "U1") (pin "A11") (pinfunction "RTXO_A11") (pintype "bidirectional"))
    )
    (net (code "96") (name "unconnected-(U1A-TFS1-PadG2)") (class "Default")
      (node (ref "U1") (pin "G2") (pinfunction "TFS1_G2") (pintype "bidirectional"))
    )
    (net (code "97") (name "unconnected-(U1A-TMR0-PadR1)") (class "Default")
      (node (ref "U1") (pin "R1") (pinfunction "TMR0_R1") (pintype "bidirectional"))
    )
    (net (code "98") (name "unconnected-(U1A-TMR1-PadP2)") (class "Default")
      (node (ref "U1") (pin "P2") (pinfunction "TMR1_P2") (pintype "bidirectional"))
    )
    (net (code "99") (name "unconnected-(U1A-TMR2-PadP1)") (class "Default")
      (node (ref "U1") (pin "P1") (pinfunction "TMR2_P1") (pintype "bidirectional"))
    )
    (net (code "100") (name "unconnected-(U1A-TSCLK1-PadG1)") (class "Default")
      (node (ref "U1") (pin "G1") (pinfunction "TSCLK1_G1") (pintype "bidirectional"))
    )
    (net (code "101") (name "unconnected-(U1A-XTAL-PadA13)") (class "Default")
      (node (ref "U1") (pin "A13") (pinfunction "XTAL_A13") (pintype "bidirectional"))
    )
    (net (code "102") (name "unconnected-(U1B-VROUT0-PadB12)") (class "Default")
      (node (ref "U1") (pin "B12") (pinfunction "VROUT0_B12") (pintype "bidirectional"))
    )
    (net (code "103") (name "unconnected-(U1B-VROUT1-PadB13)") (class "Default")
      (node (ref "U1") (pin "B13") (pinfunction "VROUT1_B13") (pintype "bidirectional"))
    )
    (net (code "104") (name "unconnected-(U1C-ADDR11-PadP17)") (class "Default")
      (node (ref "U1") (pin "P17") (pinfunction "ADDR11_P17") (pintype "bidirectional"))
    )
    (net (code "105") (name "unconnected-(U1C-ADDR14-PadR16)") (class "Default")
      (node (ref "U1") (pin "R16") (pinfunction "ADDR14_R16") (pintype "bidirectional"))
    )
    (net (code "106") (name "unconnected-(U1C-ADDR15-PadT17)") (class "Default")
      (node (ref "U1") (pin "T17") (pinfunction "ADDR15_T17") (pintype "bidirectional"))
    )
    (net (code "107") (name "unconnected-(U1C-ADDR16-PadU15)") (class "Default")
      (node (ref "U1") (pin "U15") (pinfunction "ADDR16_U15") (pintype "bidirectional"))
    )
    (net (code "108") (name "unconnected-(U1C-ADDR17-PadT15)") (class "Default")
      (node (ref "U1") (pin "T15") (pinfunction "ADDR17_T15") (pintype "bidirectional"))
    )
    (net (code "109") (name "unconnected-(U1C-ARDY-PadC16)") (class "Default")
      (node (ref "U1") (pin "C16") (pinfunction "ARDY_C16") (pintype "bidirectional"))
    )
    (net (code "110") (name "unconnected-(U1C-~{AMS0}-PadD17)") (class "Default")
      (node (ref "U1") (pin "D17") (pinfunction "~{AMS0}_D17") (pintype "bidirectional"))
    )
    (net (code "111") (name "unconnected-(U1C-~{AMS1}-PadE16)") (class "Default")
      (node (ref "U1") (pin "E16") (pinfunction "~{AMS1}_E16") (pintype "bidirectional"))
    )
    (net (code "112") (name "unconnected-(U1C-~{AMS2}-PadE17)") (class "Default")
      (node (ref "U1") (pin "E17") (pinfunction "~{AMS2}_E17") (pintype "bidirectional"))
    )
    (net (code "113") (name "unconnected-(U1C-~{AMS3}-PadF16)") (class "Default")
      (node (ref "U1") (pin "F16") (pinfunction "~{AMS3}_F16") (pintype "bidirectional"))
    )
    (net (code "114") (name "unconnected-(U1C-~{AOE}-PadF17)") (class "Default")
      (node (ref "U1") (pin "F17") (pinfunction "~{AOE}_F17") (pintype "bidirectional"))
    )
    (net (code "115") (name "unconnected-(U1C-~{ARE}-PadG16)") (class "Default")
      (node (ref "U1") (pin "G16") (pinfunction "~{ARE}_G16") (pintype "bidirectional"))
    )
    (net (code "116") (name "unconnected-(U1C-~{AWE}-PadG17)") (class "Default")
      (node (ref "U1") (pin "G17") (pinfunction "~{AWE}_G17") (pintype "bidirectional"))
    )
    (net (code "117") (name "unconnected-(U1C-~{BGH}-PadU17)") (class "Default")
      (node (ref "U1") (pin "U17") (pinfunction "~{BGH}_U17") (pintype "bidirectional"))
    )
    (net (code "118") (name "unconnected-(U1C-~{BG}-PadT13)") (class "Default")
      (node (ref "U1") (pin "T13") (pinfunction "~{BG}_T13") (pintype "bidirectional"))
    )
  )
)
